# wire_M.net
KiCad netlist of a schematic drawn in EAGLE
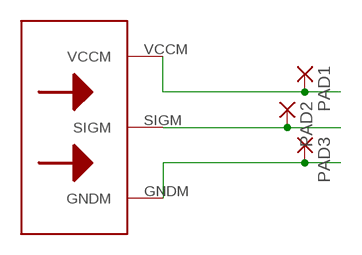
[diagram p0: schematic, sheet 1]

(export (version "E")
  (design (tool "Eeschema 10.0.6"))
  (components
    (comp (ref "PAD1")
      (value "SMD5")
      (footprint "eagle-import:SMD2,54-5,08")
      (libsource (lib "eagle-import") (part "SMD5"))
    )
    (comp (ref "PAD2")
      (value "SMD5")
      (footprint "eagle-import:SMD2,54-5,08")
      (libsource (lib "eagle-import") (part "SMD5"))
    )
    (comp (ref "PAD3")
      (value "SMD5")
      (footprint "eagle-import:SMD2,54-5,08")
      (libsource (lib "eagle-import") (part "SMD5"))
    )
    (comp (ref "U$2")
      (value "BITWIREM")
      (footprint "eagle-import:BITWIREM")
      (libsource (lib "eagle-import") (part "BITWIREM"))
    )
  )
  (nets
    (net (code "1") (name "Net-(PAD1-P)") (class "Default")
      (node (ref "PAD1") (pin "1") (pinfunction "P_1") (pintype "passive"))
      (node (ref "U$2") (pin "VCCM") (pinfunction "VCCM_VCCM") (pintype "bidirectional"))
    )
    (net (code "2") (name "Net-(PAD2-P)") (class "Default")
      (node (ref "PAD2") (pin "1") (pinfunction "P_1") (pintype "passive"))
      (node (ref "U$2") (pin "SIGM") (pinfunction "SIGM_SIGM") (pintype "bidirectional"))
    )
    (net (code "3") (name "Net-(PAD3-P)") (class "Default")
      (node (ref "PAD3") (pin "1") (pinfunction "P_1") (pintype "passive"))
      (node (ref "U$2") (pin "GNDM") (pinfunction "GNDM_GNDM") (pintype "bidirectional"))
    )
  )
)
